# Sheet1.net
KiCad netlist of a schematic drawn in Altium Designer
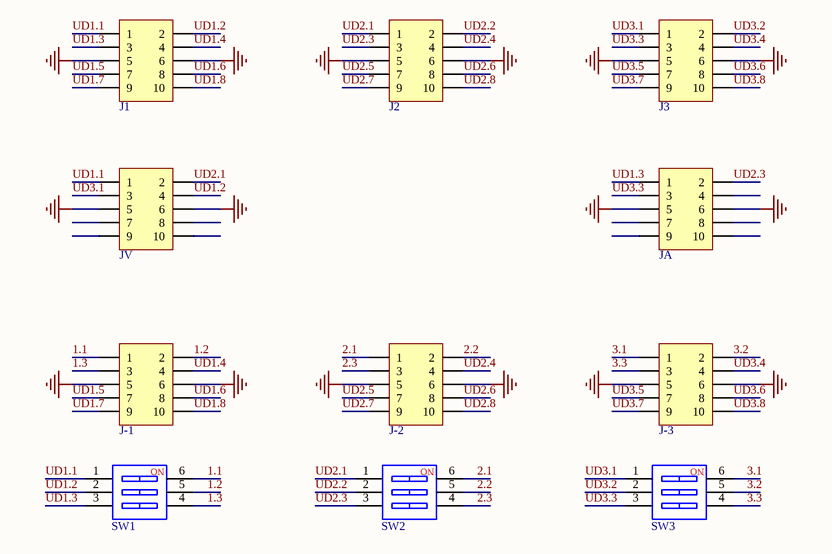
[diagram p0: Sheet1.SchDoc]

(export (version "E")
  (design (tool "Eeschema 10.0.6"))
  (components
    (comp (ref "J-1")
      (value "Header 5X2")
      (footprint "IDC2.54-LI-2x5P")
      (description "5*2P接插件")
      (libsource (lib "18 - 接插件-脚距2.54mm (100mil) ") (part "Header 5X2"))
    )
    (comp (ref "J-2")
      (value "Header 5X2")
      (footprint "IDC2.54-LI-2x5P")
      (description "5*2P接插件")
      (libsource (lib "18 - 接插件-脚距2.54mm (100mil) ") (part "Header 5X2"))
    )
    (comp (ref "J-3")
      (value "Header 5X2")
      (footprint "IDC2.54-LI-2x5P")
      (description "5*2P接插件")
      (libsource (lib "18 - 接插件-脚距2.54mm (100mil) ") (part "Header 5X2"))
    )
    (comp (ref "J1")
      (value "Header 5X2")
      (footprint "HDR2.54-LI-2x5P")
      (description "5*2P接插件")
      (libsource (lib "18 - 接插件-脚距2.54mm (100mil) ") (part "Header 5X2"))
    )
    (comp (ref "J2")
      (value "Header 5X2")
      (footprint "HDR2.54-LI-2x5P")
      (description "5*2P接插件")
      (libsource (lib "18 - 接插件-脚距2.54mm (100mil) ") (part "Header 5X2"))
    )
    (comp (ref "J3")
      (value "Header 5X2")
      (footprint "HDR2.54-LI-2x5P")
      (description "5*2P接插件")
      (libsource (lib "18 - 接插件-脚距2.54mm (100mil) ") (part "Header 5X2"))
    )
    (comp (ref "JA")
      (value "Header 5X2")
      (footprint "IDC2.54-LI-2x5P")
      (description "5*2P接插件")
      (libsource (lib "18 - 接插件-脚距2.54mm (100mil) ") (part "Header 5X2"))
    )
    (comp (ref "JV")
      (value "Header 5X2")
      (footprint "IDC2.54-LI-2x5P")
      (description "5*2P接插件")
      (libsource (lib "18 - 接插件-脚距2.54mm (100mil) ") (part "Header 5X2"))
    )
    (comp (ref "SW1")
      (value "SW-3P")
      (footprint "CSW DIP-3P")
      (description "3路编码开关")
      (libsource (lib "03 - 按键-开关-晶振-蜂鸣器") (part "SW-3P"))
    )
    (comp (ref "SW2")
      (value "SW-3P")
      (footprint "CSW DIP-3P")
      (description "3路编码开关")
      (libsource (lib "03 - 按键-开关-晶振-蜂鸣器") (part "SW-3P"))
    )
    (comp (ref "SW3")
      (value "SW-3P")
      (footprint "CSW DIP-3P")
      (description "3路编码开关")
      (libsource (lib "03 - 按键-开关-晶振-蜂鸣器") (part "SW-3P"))
    )
  )
  (nets
    (net (code "1") (name "/1.1") (class "Default")
      (node (ref "J-1") (pin "1") (pinfunction "1_1") (pintype "passive"))
      (node (ref "SW1") (pin "6") (pinfunction "6_6") (pintype "passive"))
    )
    (net (code "2") (name "/1.2") (class "Default")
      (node (ref "J-1") (pin "2") (pinfunction "2_2") (pintype "passive"))
      (node (ref "SW1") (pin "5") (pinfunction "5_5") (pintype "passive"))
    )
    (net (code "3") (name "/1.3") (class "Default")
      (node (ref "J-1") (pin "3") (pinfunction "3_3") (pintype "passive"))
      (node (ref "SW1") (pin "4") (pinfunction "4_4") (pintype "passive"))
    )
    (net (code "4") (name "/2.1") (class "Default")
      (node (ref "J-2") (pin "1") (pinfunction "1_1") (pintype "passive"))
      (node (ref "SW2") (pin "6") (pinfunction "6_6") (pintype "passive"))
    )
    (net (code "5") (name "/2.2") (class "Default")
      (node (ref "J-2") (pin "2") (pinfunction "2_2") (pintype "passive"))
      (node (ref "SW2") (pin "5") (pinfunction "5_5") (pintype "passive"))
    )
    (net (code "6") (name "/2.3") (class "Default")
      (node (ref "J-2") (pin "3") (pinfunction "3_3") (pintype "passive"))
      (node (ref "SW2") (pin "4") (pinfunction "4_4") (pintype "passive"))
    )
    (net (code "7") (name "/3.1") (class "Default")
      (node (ref "J-3") (pin "1") (pinfunction "1_1") (pintype "passive"))
      (node (ref "SW3") (pin "6") (pinfunction "6_6") (pintype "passive"))
    )
    (net (code "8") (name "/3.2") (class "Default")
      (node (ref "J-3") (pin "2") (pinfunction "2_2") (pintype "passive"))
      (node (ref "SW3") (pin "5") (pinfunction "5_5") (pintype "passive"))
    )
    (net (code "9") (name "/3.3") (class "Default")
      (node (ref "J-3") (pin "3") (pinfunction "3_3") (pintype "passive"))
      (node (ref "SW3") (pin "4") (pinfunction "4_4") (pintype "passive"))
    )
    (net (code "10") (name "/UD1.1") (class "Default")
      (node (ref "J1") (pin "1") (pinfunction "1_1") (pintype "passive"))
      (node (ref "JV") (pin "1") (pinfunction "1_1") (pintype "passive"))
      (node (ref "SW1") (pin "1") (pinfunction "1_1") (pintype "passive"))
    )
    (net (code "11") (name "/UD1.2") (class "Default")
      (node (ref "J1") (pin "2") (pinfunction "2_2") (pintype "passive"))
      (node (ref "JV") (pin "4") (pinfunction "4_4") (pintype "passive"))
      (node (ref "SW1") (pin "2") (pinfunction "2_2") (pintype "passive"))
    )
    (net (code "12") (name "/UD1.3") (class "Default")
      (node (ref "J1") (pin "3") (pinfunction "3_3") (pintype "passive"))
      (node (ref "JA") (pin "1") (pinfunction "1_1") (pintype "passive"))
      (node (ref "SW1") (pin "3") (pinfunction "3_3") (pintype "passive"))
    )
    (net (code "13") (name "/UD1.4") (class "Default")
      (node (ref "J-1") (pin "4") (pinfunction "4_4") (pintype "passive"))
      (node (ref "J1") (pin "4") (pinfunction "4_4") (pintype "passive"))
    )
    (net (code "14") (name "/UD1.5") (class "Default")
      (node (ref "J-1") (pin "7") (pinfunction "7_7") (pintype "passive"))
      (node (ref "J1") (pin "7") (pinfunction "7_7") (pintype "passive"))
    )
    (net (code "15") (name "/UD1.6") (class "Default")
      (node (ref "J-1") (pin "8") (pinfunction "8_8") (pintype "passive"))
      (node (ref "J1") (pin "8") (pinfunction "8_8") (pintype "passive"))
    )
    (net (code "16") (name "/UD1.7") (class "Default")
      (node (ref "J-1") (pin "9") (pinfunction "9_9") (pintype "passive"))
      (node (ref "J1") (pin "9") (pinfunction "9_9") (pintype "passive"))
    )
    (net (code "17") (name "/UD1.8") (class "Default")
      (node (ref "J-1") (pin "10") (pinfunction "10_10") (pintype "passive"))
      (node (ref "J1") (pin "10") (pinfunction "10_10") (pintype "passive"))
    )
    (net (code "18") (name "/UD2.1") (class "Default")
      (node (ref "J2") (pin "1") (pinfunction "1_1") (pintype "passive"))
      (node (ref "JV") (pin "2") (pinfunction "2_2") (pintype "passive"))
      (node (ref "SW2") (pin "1") (pinfunction "1_1") (pintype "passive"))
    )
    (net (code "19") (name "/UD2.2") (class "Default")
      (node (ref "J2") (pin "2") (pinfunction "2_2") (pintype "passive"))
      (node (ref "SW2") (pin "2") (pinfunction "2_2") (pintype "passive"))
    )
    (net (code "20") (name "/UD2.3") (class "Default")
      (node (ref "J2") (pin "3") (pinfunction "3_3") (pintype "passive"))
      (node (ref "JA") (pin "2") (pinfunction "2_2") (pintype "passive"))
      (node (ref "SW2") (pin "3") (pinfunction "3_3") (pintype "passive"))
    )
    (net (code "21") (name "/UD2.4") (class "Default")
      (node (ref "J-2") (pin "4") (pinfunction "4_4") (pintype "passive"))
      (node (ref "J2") (pin "4") (pinfunction "4_4") (pintype "passive"))
    )
    (net (code "22") (name "/UD2.5") (class "Default")
      (node (ref "J-2") (pin "7") (pinfunction "7_7") (pintype "passive"))
      (node (ref "J2") (pin "7") (pinfunction "7_7") (pintype "passive"))
    )
    (net (code "23") (name "/UD2.6") (class "Default")
      (node (ref "J-2") (pin "8") (pinfunction "8_8") (pintype "passive"))
      (node (ref "J2") (pin "8") (pinfunction "8_8") (pintype "passive"))
    )
    (net (code "24") (name "/UD2.7") (class "Default")
      (node (ref "J-2") (pin "9") (pinfunction "9_9") (pintype "passive"))
      (node (ref "J2") (pin "9") (pinfunction "9_9") (pintype "passive"))
    )
    (net (code "25") (name "/UD2.8") (class "Default")
      (node (ref "J-2") (pin "10") (pinfunction "10_10") (pintype "passive"))
      (node (ref "J2") (pin "10") (pinfunction "10_10") (pintype "passive"))
    )
    (net (code "26") (name "/UD3.1") (class "Default")
      (node (ref "J3") (pin "1") (pinfunction "1_1") (pintype "passive"))
      (node (ref "JV") (pin "3") (pinfunction "3_3") (pintype "passive"))
      (node (ref "SW3") (pin "1") (pinfunction "1_1") (pintype "passive"))
    )
    (net (code "27") (name "/UD3.2") (class "Default")
      (node (ref "J3") (pin "2") (pinfunction "2_2") (pintype "passive"))
      (node (ref "SW3") (pin "2") (pinfunction "2_2") (pintype "passive"))
    )
    (net (code "28") (name "/UD3.3") (class "Default")
      (node (ref "J3") (pin "3") (pinfunction "3_3") (pintype "passive"))
      (node (ref "JA") (pin "3") (pinfunction "3_3") (pintype "passive"))
      (node (ref "SW3") (pin "3") (pinfunction "3_3") (pintype "passive"))
    )
    (net (code "29") (name "/UD3.4") (class "Default")
      (node (ref "J-3") (pin "4") (pinfunction "4_4") (pintype "passive"))
      (node (ref "J3") (pin "4") (pinfunction "4_4") (pintype "passive"))
    )
    (net (code "30") (name "/UD3.5") (class "Default")
      (node (ref "J-3") (pin "7") (pinfunction "7_7") (pintype "passive"))
      (node (ref "J3") (pin "7") (pinfunction "7_7") (pintype "passive"))
    )
    (net (code "31") (name "/UD3.6") (class "Default")
      (node (ref "J-3") (pin "8") (pinfunction "8_8") (pintype "passive"))
      (node (ref "J3") (pin "8") (pinfunction "8_8") (pintype "passive"))
    )
    (net (code "32") (name "/UD3.7") (class "Default")
      (node (ref "J-3") (pin "9") (pinfunction "9_9") (pintype "passive"))
      (node (ref "J3") (pin "9") (pinfunction "9_9") (pintype "passive"))
    )
    (net (code "33") (name "/UD3.8") (class "Default")
      (node (ref "J-3") (pin "10") (pinfunction "10_10") (pintype "passive"))
      (node (ref "J3") (pin "10") (pinfunction "10_10") (pintype "passive"))
    )
    (net (code "34") (name "GND") (class "Default")
      (node (ref "J-1") (pin "5") (pinfunction "5_5") (pintype "passive"))
      (node (ref "J-1") (pin "6") (pinfunction "6_6") (pintype "passive"))
      (node (ref "J-2") (pin "5") (pinfunction "5_5") (pintype "passive"))
      (node (ref "J-2") (pin "6") (pinfunction "6_6") (pintype "passive"))
      (node (ref "J-3") (pin "5") (pinfunction "5_5") (pintype "passive"))
      (node (ref "J-3") (pin "6") (pinfunction "6_6") (pintype "passive"))
      (node (ref "J1") (pin "5") (pinfunction "5_5") (pintype "passive"))
      (node (ref "J1") (pin "6") (pinfunction "6_6") (pintype "passive"))
      (node (ref "J2") (pin "5") (pinfunction "5_5") (pintype "passive"))
      (node (ref "J2") (pin "6") (pinfunction "6_6") (pintype "passive"))
      (node (ref "J3") (pin "5") (pinfunction "5_5") (pintype "passive"))
      (node (ref "J3") (pin "6") (pinfunction "6_6") (pintype "passive"))
      (node (ref "JA") (pin "5") (pinfunction "5_5") (pintype "passive"))
      (node (ref "JA") (pin "6") (pinfunction "6_6") (pintype "passive"))
      (node (ref "JV") (pin "5") (pinfunction "5_5") (pintype "passive"))
      (node (ref "JV") (pin "6") (pinfunction "6_6") (pintype "passive"))
    )
    (net (code "35") (name "unconnected-(JA-Pad4)") (class "Default")
      (node (ref "JA") (pin "4") (pinfunction "4_4") (pintype "passive"))
    )
    (net (code "36") (name "unconnected-(JA-Pad7)") (class "Default")
      (node (ref "JA") (pin "7") (pinfunction "7_7") (pintype "passive"))
    )
    (net (code "37") (name "unconnected-(JA-Pad8)") (class "Default")
      (node (ref "JA") (pin "8") (pinfunction "8_8") (pintype "passive"))
    )
    (net (code "38") (name "unconnected-(JA-Pad9)") (class "Default")
      (node (ref "JA") (pin "9") (pinfunction "9_9") (pintype "passive"))
    )
    (net (code "39") (name "unconnected-(JA-Pad10)") (class "Default")
      (node (ref "JA") (pin "10") (pinfunction "10_10") (pintype "passive"))
    )
    (net (code "40") (name "unconnected-(JV-Pad7)") (class "Default")
      (node (ref "JV") (pin "7") (pinfunction "7_7") (pintype "passive"))
    )
    (net (code "41") (name "unconnected-(JV-Pad8)") (class "Default")
      (node (ref "JV") (pin "8") (pinfunction "8_8") (pintype "passive"))
    )
    (net (code "42") (name "unconnected-(JV-Pad9)") (class "Default")
      (node (ref "JV") (pin "9") (pinfunction "9_9") (pintype "passive"))
    )
    (net (code "43") (name "unconnected-(JV-Pad10)") (class "Default")
      (node (ref "JV") (pin "10") (pinfunction "10_10") (pintype "passive"))
    )
  )
)
